# SCH_ACSI2STM-MINI_2026-07-24.net
KiCad netlist of a schematic drawn in EasyEDA
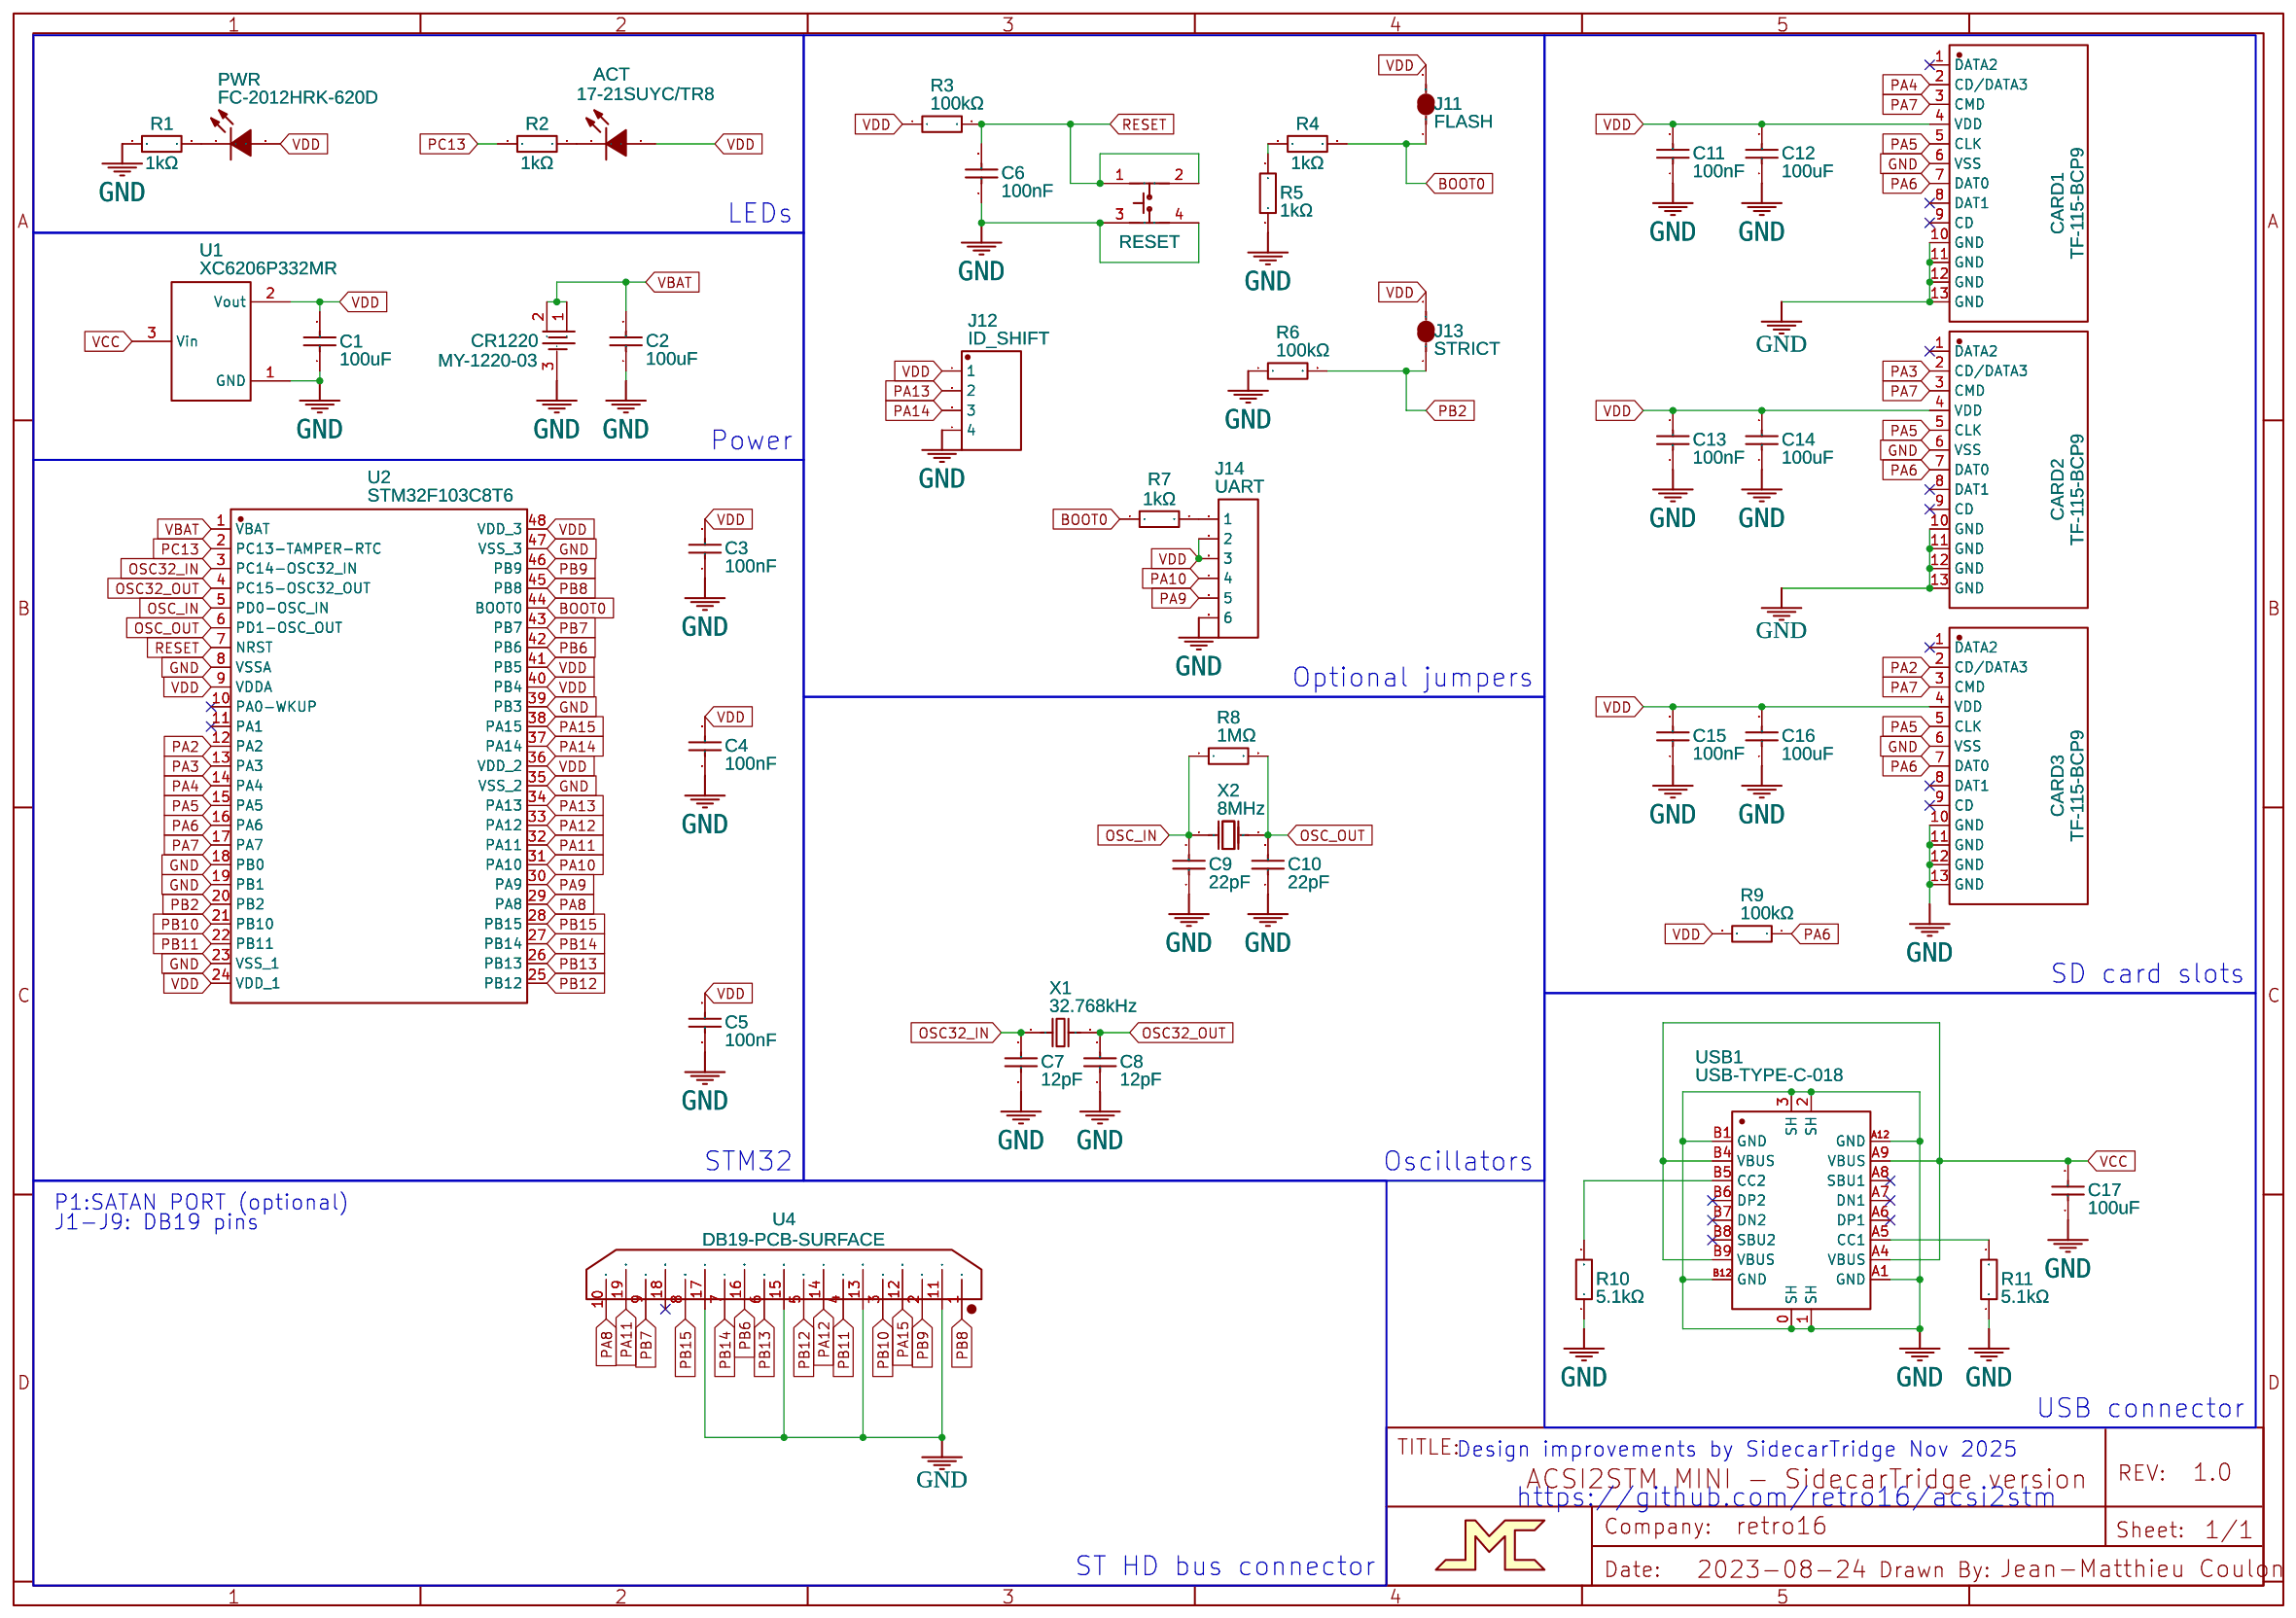
[diagram p0: schematic sheet]

(export (version "E")
  (design (tool "Eeschema 10.0.6"))
  (components
    (comp (ref "ACT")
      (value "17-21SUYC/TR8")
      (fields (field (name "Manufacturer Part") "KT-0805黄灯") (field (name "Manufacturer") "KENTO"))
      (libsource (lib "") (part "17-21SUYC/TR8"))
    )
    (comp (ref "C1")
      (value "100uF")
      (fields
        (field (name "Manufacturer Part") "CL31A107MQHNNNE")
        (field (name "Manufacturer") "SAMSUNG(三星)")
      )
      (libsource (lib "") (part "CL31A107MQHNNNE"))
    )
    (comp (ref "C2")
      (value "100uF")
      (fields
        (field (name "Manufacturer Part") "CL31A107MQHNNNE")
        (field (name "Manufacturer") "SAMSUNG(三星)")
      )
      (libsource (lib "") (part "CL31A107MQHNNNE"))
    )
    (comp (ref "C3")
      (value "100nF")
      (fields
        (field (name "Manufacturer Part") "CL05B104KO5NNNC")
        (field (name "Manufacturer") "SAMSUNG(三星)")
      )
      (libsource (lib "") (part "CL05B104KO5NNNC"))
    )
    (comp (ref "C4")
      (value "100nF")
      (fields
        (field (name "Manufacturer Part") "CL05B104KO5NNNC")
        (field (name "Manufacturer") "SAMSUNG(三星)")
      )
      (libsource (lib "") (part "CL05B104KO5NNNC"))
    )
    (comp (ref "C5")
      (value "100nF")
      (fields
        (field (name "Manufacturer Part") "CL05B104KO5NNNC")
        (field (name "Manufacturer") "SAMSUNG(三星)")
      )
      (libsource (lib "") (part "CL05B104KO5NNNC"))
    )
    (comp (ref "C6")
      (value "100nF")
      (fields
        (field (name "Manufacturer Part") "CL05B104KO5NNNC")
        (field (name "Manufacturer") "SAMSUNG(三星)")
      )
      (libsource (lib "") (part "CL05B104KO5NNNC"))
    )
    (comp (ref "C7")
      (value "12pF")
      (fields (field (name "Manufacturer Part") "0402CG120J500NT") (field (name "Manufacturer") "FH(风华)"))
      (libsource (lib "") (part "0402CG120J500NT"))
    )
    (comp (ref "C8")
      (value "12pF")
      (fields (field (name "Manufacturer Part") "0402CG120J500NT") (field (name "Manufacturer") "FH(风华)"))
      (libsource (lib "") (part "0402CG120J500NT"))
    )
    (comp (ref "C9")
      (value "22pF")
      (fields (field (name "Manufacturer Part") "0402CG220J500NT") (field (name "Manufacturer") "FH(风华)"))
      (libsource (lib "") (part "0402CG220J500NT"))
    )
    (comp (ref "C10")
      (value "22pF")
      (fields (field (name "Manufacturer Part") "0402CG220J500NT") (field (name "Manufacturer") "FH(风华)"))
      (libsource (lib "") (part "0402CG220J500NT"))
    )
    (comp (ref "C11")
      (value "100nF")
      (fields
        (field (name "Manufacturer Part") "CL05B104KO5NNNC")
        (field (name "Manufacturer") "SAMSUNG(三星)")
      )
      (libsource (lib "") (part "CL05B104KO5NNNC"))
    )
    (comp (ref "C12")
      (value "100uF")
      (fields
        (field (name "Manufacturer Part") "CL31A107MQHNNNE")
        (field (name "Manufacturer") "SAMSUNG(三星)")
      )
      (libsource (lib "") (part "CL31A107MQHNNNE"))
    )
    (comp (ref "C13")
      (value "100nF")
      (fields
        (field (name "Manufacturer Part") "CL05B104KO5NNNC")
        (field (name "Manufacturer") "SAMSUNG(三星)")
      )
      (libsource (lib "") (part "CL05B104KO5NNNC"))
    )
    (comp (ref "C14")
      (value "100uF")
      (fields
        (field (name "Manufacturer Part") "CL31A107MQHNNNE")
        (field (name "Manufacturer") "SAMSUNG(三星)")
      )
      (libsource (lib "") (part "CL31A107MQHNNNE"))
    )
    (comp (ref "C15")
      (value "100nF")
      (fields
        (field (name "Manufacturer Part") "CL31B104KBCNNNC")
        (field (name "Manufacturer") "SAMSUNG(三星)")
      )
      (libsource (lib "") (part "CL31B104KBCNNNC"))
    )
    (comp (ref "C16")
      (value "100uF")
      (fields
        (field (name "Manufacturer Part") "CL31A107MQHNNNE")
        (field (name "Manufacturer") "SAMSUNG(三星)")
      )
      (libsource (lib "") (part "CL31A107MQHNNNE"))
    )
    (comp (ref "C17")
      (value "100uF")
      (fields
        (field (name "Manufacturer Part") "CL31A107MQHNNNE")
        (field (name "Manufacturer") "SAMSUNG(三星)")
      )
      (libsource (lib "") (part "CL31A107MQHNNNE"))
    )
    (comp (ref "CARD1")
      (value "TF-115-BCP9")
      (fields (field (name "Manufacturer") "XUNPU(讯普)"))
      (libsource (lib "") (part "TF-115-BCP9"))
    )
    (comp (ref "CARD2")
      (value "TF-115-BCP9")
      (fields (field (name "Manufacturer") "XUNPU(讯普)"))
      (libsource (lib "") (part "TF-115-BCP9"))
    )
    (comp (ref "CARD3")
      (value "TF-115-BCP9")
      (fields (field (name "Manufacturer") "XUNPU(讯普)"))
      (libsource (lib "") (part "TF-115-BCP9"))
    )
    (comp (ref "CR1220")
      (value "MY-1220-03")
      (fields (field (name "Manufacturer") "MYOUNG(美阳)"))
      (libsource (lib "") (part "MY-1220-03"))
    )
    (comp (ref "J11") (value "FLASH") (libsource (lib "") (part "SOLDERJUMPERNO")))
    (comp (ref "J12") (value "ID_SHIFT") (libsource (lib "") (part "SJ-4PAD")))
    (comp (ref "J13") (value "STRICT") (libsource (lib "") (part "SOLDERJUMPERNO")))
    (comp (ref "J14") (value "UART") (libsource (lib "") (part "HDR-F-2.54_1x6")))
    (comp (ref "PWR")
      (value "FC-2012HRK-620D")
      (fields (field (name "Manufacturer Part") "NCD0805R1") (field (name "Manufacturer") "国星光电"))
      (libsource (lib "") (part "FC-2012HRK-620D"))
    )
    (comp (ref "R1")
      (value "1kΩ")
      (fields
        (field (name "Manufacturer Part") "0402WGF1001TCE")
        (field (name "Manufacturer") "UNI-ROYAL(厚声)")
      )
      (libsource (lib "") (part "0402WGF1001TCE"))
    )
    (comp (ref "R2")
      (value "1kΩ")
      (fields
        (field (name "Manufacturer Part") "0402WGF1001TCE")
        (field (name "Manufacturer") "UNI-ROYAL(厚声)")
      )
      (libsource (lib "") (part "0402WGF1001TCE"))
    )
    (comp (ref "R3")
      (value "100kΩ")
      (fields
        (field (name "Manufacturer Part") "0402WGF1003TCE")
        (field (name "Manufacturer") "UNI-ROYAL(厚声)")
      )
      (libsource (lib "") (part "0402WGF1003TCE"))
    )
    (comp (ref "R4")
      (value "1kΩ")
      (fields
        (field (name "Manufacturer Part") "0402WGF1001TCE")
        (field (name "Manufacturer") "UNI-ROYAL(厚声)")
      )
      (libsource (lib "") (part "0402WGF1001TCE"))
    )
    (comp (ref "R5")
      (value "1kΩ")
      (fields
        (field (name "Manufacturer Part") "0402WGF1001TCE")
        (field (name "Manufacturer") "UNI-ROYAL(厚声)")
      )
      (libsource (lib "") (part "0402WGF1001TCE_1"))
    )
    (comp (ref "R6")
      (value "100kΩ")
      (fields
        (field (name "Manufacturer Part") "0402WGF1003TCE")
        (field (name "Manufacturer") "UNI-ROYAL(厚声)")
      )
      (libsource (lib "") (part "0402WGF1003TCE"))
    )
    (comp (ref "R7")
      (value "1kΩ")
      (fields
        (field (name "Manufacturer Part") "0402WGF1001TCE")
        (field (name "Manufacturer") "UNI-ROYAL(厚声)")
      )
      (libsource (lib "") (part "0402WGF1001TCE"))
    )
    (comp (ref "R8")
      (value "1MΩ")
      (fields
        (field (name "Manufacturer Part") "0402WGF1004TCE")
        (field (name "Manufacturer") "UNI-ROYAL(厚声)")
      )
      (libsource (lib "") (part "0402WGF1004TCE"))
    )
    (comp (ref "R9")
      (value "100kΩ")
      (fields
        (field (name "Manufacturer Part") "0402WGF1003TCE")
        (field (name "Manufacturer") "UNI-ROYAL(厚声)")
      )
      (libsource (lib "") (part "0402WGF1003TCE_1"))
    )
    (comp (ref "R10")
      (value "5.1kΩ")
      (fields
        (field (name "Manufacturer Part") "0402WGF5101TCE")
        (field (name "Manufacturer") "UNI-ROYAL(厚声)")
      )
      (libsource (lib "") (part "0402WGF5101TCE"))
    )
    (comp (ref "R11")
      (value "5.1kΩ")
      (fields
        (field (name "Manufacturer Part") "0402WGF5101TCE")
        (field (name "Manufacturer") "UNI-ROYAL(厚声)")
      )
      (libsource (lib "") (part "0402WGF5101TCE"))
    )
    (comp (ref "RESET")
      (value "SKRPABE010")
      (fields (field (name "Manufacturer") "ALPSALPINE(阿尔卑斯阿尔派)"))
      (libsource (lib "") (part "SKRPABE010"))
    )
    (comp (ref "U1")
      (value "XC6206P332MR")
      (fields (field (name "Manufacturer") "TOREX(特瑞仕)"))
      (libsource (lib "") (part "XC6206P332MR"))
    )
    (comp (ref "U2")
      (value "STM32F103C8T6")
      (fields (field (name "Manufacturer") "ST(意法半导体)"))
      (libsource (lib "") (part "STM32F103C8T6"))
    )
    (comp (ref "U3") (value "JMC_LOGO") (libsource (lib "") (part "JMC_LOGO")))
    (comp (ref "U4") (value "DB19-PCB-SURFACE") (libsource (lib "") (part "DB19-PCB-SURFACE")))
    (comp (ref "USB1")
      (value "USB-TYPE-C-018")
      (fields (field (name "Manufacturer") "DEALON(德艺隆)"))
      (libsource (lib "") (part "USB-TYPE-C-018"))
    )
    (comp (ref "X1")
      (value "32.768kHz")
      (fields (field (name "Manufacturer Part") "Q13FC1350000400") (field (name "Manufacturer") "EPSON(爱普生)"))
      (libsource (lib "") (part "Q13FC1350000400"))
    )
    (comp (ref "X2")
      (value "8MHz")
      (fields (field (name "Manufacturer Part") "X50328MSB2GI") (field (name "Manufacturer") "YXC(扬兴晶振)"))
      (libsource (lib "") (part "X50328MSB2GI"))
    )
  )
  (nets
    (net (code "1") (name "BOOT0") (class "Default")
      (node (ref "J11") (pin "1") (pinfunction "1_1") (pintype "unspecified"))
      (node (ref "R4") (pin "2") (pinfunction "2_2") (pintype "input"))
      (node (ref "R7") (pin "1") (pinfunction "1_1") (pintype "input"))
      (node (ref "U2") (pin "44") (pinfunction "BOOT0_44") (pintype "unspecified"))
    )
    (net (code "2") (name "GND") (class "Default")
      (node (ref "C1") (pin "1") (pinfunction "1_1") (pintype "input"))
      (node (ref "C10") (pin "1") (pinfunction "1_1") (pintype "input"))
      (node (ref "C11") (pin "1") (pinfunction "1_1") (pintype "input"))
      (node (ref "C12") (pin "1") (pinfunction "1_1") (pintype "input"))
      (node (ref "C13") (pin "1") (pinfunction "1_1") (pintype "input"))
      (node (ref "C14") (pin "1") (pinfunction "1_1") (pintype "input"))
      (node (ref "C15") (pin "1") (pinfunction "1_1") (pintype "input"))
      (node (ref "C16") (pin "1") (pinfunction "1_1") (pintype "input"))
      (node (ref "C17") (pin "1") (pinfunction "1_1") (pintype "input"))
      (node (ref "C2") (pin "1") (pinfunction "1_1") (pintype "input"))
      (node (ref "C3") (pin "1") (pinfunction "1_1") (pintype "input"))
      (node (ref "C4") (pin "1") (pinfunction "1_1") (pintype "input"))
      (node (ref "C5") (pin "1") (pinfunction "1_1") (pintype "input"))
      (node (ref "C6") (pin "1") (pinfunction "1_1") (pintype "input"))
      (node (ref "C7") (pin "2") (pinfunction "2_2") (pintype "input"))
      (node (ref "C8") (pin "2") (pinfunction "2_2") (pintype "input"))
      (node (ref "C9") (pin "1") (pinfunction "1_1") (pintype "input"))
      (node (ref "CARD1") (pin "10") (pinfunction "GND_10") (pintype "unspecified"))
      (node (ref "CARD1") (pin "11") (pinfunction "GND_11") (pintype "unspecified"))
      (node (ref "CARD1") (pin "12") (pinfunction "GND_12") (pintype "unspecified"))
      (node (ref "CARD1") (pin "13") (pinfunction "GND_13") (pintype "unspecified"))
      (node (ref "CARD1") (pin "6") (pinfunction "VSS_6") (pintype "unspecified"))
      (node (ref "CARD2") (pin "10") (pinfunction "GND_10") (pintype "unspecified"))
      (node (ref "CARD2") (pin "11") (pinfunction "GND_11") (pintype "unspecified"))
      (node (ref "CARD2") (pin "12") (pinfunction "GND_12") (pintype "unspecified"))
      (node (ref "CARD2") (pin "13") (pinfunction "GND_13") (pintype "unspecified"))
      (node (ref "CARD2") (pin "6") (pinfunction "VSS_6") (pintype "unspecified"))
      (node (ref "CARD3") (pin "10") (pinfunction "GND_10") (pintype "unspecified"))
      (node (ref "CARD3") (pin "11") (pinfunction "GND_11") (pintype "unspecified"))
      (node (ref "CARD3") (pin "12") (pinfunction "GND_12") (pintype "unspecified"))
      (node (ref "CARD3") (pin "13") (pinfunction "GND_13") (pintype "unspecified"))
      (node (ref "CARD3") (pin "6") (pinfunction "VSS_6") (pintype "unspecified"))
      (node (ref "CR1220") (pin "3") (pinfunction "-_3") (pintype "input"))
      (node (ref "J12") (pin "4") (pinfunction "4_4") (pintype "unspecified"))
      (node (ref "J14") (pin "6") (pinfunction "6_6") (pintype "input"))
      (node (ref "R1") (pin "1") (pinfunction "1_1") (pintype "input"))
      (node (ref "R10") (pin "1") (pinfunction "1_1") (pintype "input"))
      (node (ref "R11") (pin "1") (pinfunction "1_1") (pintype "input"))
      (node (ref "R5") (pin "1") (pinfunction "1_1") (pintype "input"))
      (node (ref "R6") (pin "1") (pinfunction "1_1") (pintype "input"))
      (node (ref "RESET") (pin "3") (pinfunction "3_3") (pintype "unspecified"))
      (node (ref "RESET") (pin "4") (pinfunction "4_4") (pintype "unspecified"))
      (node (ref "U1") (pin "1") (pinfunction "GND_1") (pintype "unspecified"))
      (node (ref "U2") (pin "18") (pinfunction "PB0_18") (pintype "unspecified"))
      (node (ref "U2") (pin "19") (pinfunction "PB1_19") (pintype "unspecified"))
      (node (ref "U2") (pin "23") (pinfunction "VSS_1_23") (pintype "unspecified"))
      (node (ref "U2") (pin "35") (pinfunction "VSS_2_35") (pintype "unspecified"))
      (node (ref "U2") (pin "39") (pinfunction "PB3_39") (pintype "unspecified"))
      (node (ref "U2") (pin "47") (pinfunction "VSS_3_47") (pintype "unspecified"))
      (node (ref "U2") (pin "8") (pinfunction "VSSA_8") (pintype "unspecified"))
      (node (ref "U4") (pin "11") (pinfunction "11_11") (pintype "unspecified"))
      (node (ref "U4") (pin "13") (pinfunction "13_13") (pintype "unspecified"))
      (node (ref "U4") (pin "15") (pinfunction "15_15") (pintype "unspecified"))
      (node (ref "U4") (pin "17") (pinfunction "17_17") (pintype "unspecified"))
      (node (ref "USB1") (pin "0") (pinfunction "SH_0") (pintype "unspecified"))
      (node (ref "USB1") (pin "1") (pinfunction "SH_1") (pintype "unspecified"))
      (node (ref "USB1") (pin "2") (pinfunction "SH_2") (pintype "unspecified"))
      (node (ref "USB1") (pin "3") (pinfunction "SH_3") (pintype "unspecified"))
      (node (ref "USB1") (pin "A1") (pinfunction "GND_A1") (pintype "unspecified"))
      (node (ref "USB1") (pin "A12") (pinfunction "GND_A12") (pintype "unspecified"))
      (node (ref "USB1") (pin "B1") (pinfunction "GND_B1") (pintype "unspecified"))
      (node (ref "USB1") (pin "B12") (pinfunction "GND_B12") (pintype "unspecified"))
    )
    (net (code "3") (name "Net-(ACT--)") (class "Default")
      (node (ref "ACT") (pin "2") (pinfunction "-_2") (pintype "unspecified"))
      (node (ref "R2") (pin "2") (pinfunction "2_2") (pintype "input"))
    )
    (net (code "4") (name "Net-(J14-Pad1)") (class "Default")
      (node (ref "J14") (pin "1") (pinfunction "1_1") (pintype "input"))
      (node (ref "R7") (pin "2") (pinfunction "2_2") (pintype "input"))
    )
    (net (code "5") (name "Net-(PWR--)") (class "Default")
      (node (ref "PWR") (pin "1") (pinfunction "-_1") (pintype "unspecified"))
      (node (ref "R1") (pin "2") (pinfunction "2_2") (pintype "input"))
    )
    (net (code "6") (name "Net-(R4-Pad1)") (class "Default")
      (node (ref "R4") (pin "1") (pinfunction "1_1") (pintype "input"))
      (node (ref "R5") (pin "2") (pinfunction "2_2") (pintype "input"))
    )
    (net (code "7") (name "Net-(USB1-CC1)") (class "Default")
      (node (ref "R11") (pin "2") (pinfunction "2_2") (pintype "input"))
      (node (ref "USB1") (pin "A5") (pinfunction "CC1_A5") (pintype "unspecified"))
    )
    (net (code "8") (name "Net-(USB1-CC2)") (class "Default")
      (node (ref "R10") (pin "2") (pinfunction "2_2") (pintype "input"))
      (node (ref "USB1") (pin "B5") (pinfunction "CC2_B5") (pintype "unspecified"))
    )
    (net (code "9") (name "OSC32_IN") (class "Default")
      (node (ref "C7") (pin "1") (pinfunction "1_1") (pintype "input"))
      (node (ref "U2") (pin "3") (pinfunction "PC14-OSC32_IN_3") (pintype "unspecified"))
      (node (ref "X1") (pin "1") (pinfunction "1_1") (pintype "unspecified"))
    )
    (net (code "10") (name "OSC32_OUT") (class "Default")
      (node (ref "C8") (pin "1") (pinfunction "1_1") (pintype "input"))
      (node (ref "U2") (pin "4") (pinfunction "PC15-OSC32_OUT_4") (pintype "unspecified"))
      (node (ref "X1") (pin "2") (pinfunction "2_2") (pintype "unspecified"))
    )
    (net (code "11") (name "OSC_IN") (class "Default")
      (node (ref "C9") (pin "2") (pinfunction "2_2") (pintype "input"))
      (node (ref "R8") (pin "1") (pinfunction "1_1") (pintype "input"))
      (node (ref "U2") (pin "5") (pinfunction "PD0-OSC_IN_5") (pintype "unspecified"))
      (node (ref "X2") (pin "1") (pinfunction "OSC1_1") (pintype "input"))
    )
    (net (code "12") (name "OSC_OUT") (class "Default")
      (node (ref "C10") (pin "2") (pinfunction "2_2") (pintype "input"))
      (node (ref "R8") (pin "2") (pinfunction "2_2") (pintype "input"))
      (node (ref "U2") (pin "6") (pinfunction "PD1-OSC_OUT_6") (pintype "unspecified"))
      (node (ref "X2") (pin "2") (pinfunction "OSC2_2") (pintype "input"))
    )
    (net (code "13") (name "PA2") (class "Default")
      (node (ref "CARD3") (pin "2") (pinfunction "CD/DATA3_2") (pintype "unspecified"))
      (node (ref "U2") (pin "12") (pinfunction "PA2_12") (pintype "unspecified"))
    )
    (net (code "14") (name "PA3") (class "Default")
      (node (ref "CARD2") (pin "2") (pinfunction "CD/DATA3_2") (pintype "unspecified"))
      (node (ref "U2") (pin "13") (pinfunction "PA3_13") (pintype "unspecified"))
    )
    (net (code "15") (name "PA4") (class "Default")
      (node (ref "CARD1") (pin "2") (pinfunction "CD/DATA3_2") (pintype "unspecified"))
      (node (ref "U2") (pin "14") (pinfunction "PA4_14") (pintype "unspecified"))
    )
    (net (code "16") (name "PA5") (class "Default")
      (node (ref "CARD1") (pin "5") (pinfunction "CLK_5") (pintype "unspecified"))
      (node (ref "CARD2") (pin "5") (pinfunction "CLK_5") (pintype "unspecified"))
      (node (ref "CARD3") (pin "5") (pinfunction "CLK_5") (pintype "unspecified"))
      (node (ref "U2") (pin "15") (pinfunction "PA5_15") (pintype "unspecified"))
    )
    (net (code "17") (name "PA6") (class "Default")
      (node (ref "CARD1") (pin "7") (pinfunction "DAT0_7") (pintype "unspecified"))
      (node (ref "CARD2") (pin "7") (pinfunction "DAT0_7") (pintype "unspecified"))
      (node (ref "CARD3") (pin "7") (pinfunction "DAT0_7") (pintype "unspecified"))
      (node (ref "R9") (pin "1") (pinfunction "1_1") (pintype "input"))
      (node (ref "U2") (pin "16") (pinfunction "PA6_16") (pintype "unspecified"))
    )
    (net (code "18") (name "PA7") (class "Default")
      (node (ref "CARD1") (pin "3") (pinfunction "CMD_3") (pintype "unspecified"))
      (node (ref "CARD2") (pin "3") (pinfunction "CMD_3") (pintype "unspecified"))
      (node (ref "CARD3") (pin "3") (pinfunction "CMD_3") (pintype "unspecified"))
      (node (ref "U2") (pin "17") (pinfunction "PA7_17") (pintype "unspecified"))
    )
    (net (code "19") (name "PA8") (class "Default")
      (node (ref "U2") (pin "29") (pinfunction "PA8_29") (pintype "unspecified"))
      (node (ref "U4") (pin "10") (pinfunction "10_10") (pintype "unspecified"))
    )
    (net (code "20") (name "PA9") (class "Default")
      (node (ref "J14") (pin "5") (pinfunction "5_5") (pintype "input"))
      (node (ref "U2") (pin "30") (pinfunction "PA9_30") (pintype "unspecified"))
    )
    (net (code "21") (name "PA10") (class "Default")
      (node (ref "J14") (pin "4") (pinfunction "4_4") (pintype "input"))
      (node (ref "U2") (pin "31") (pinfunction "PA10_31") (pintype "unspecified"))
    )
    (net (code "22") (name "PA11") (class "Default")
      (node (ref "U2") (pin "32") (pinfunction "PA11_32") (pintype "unspecified"))
      (node (ref "U4") (pin "19") (pinfunction "19_19") (pintype "unspecified"))
    )
    (net (code "23") (name "PA12") (class "Default")
      (node (ref "U2") (pin "33") (pinfunction "PA12_33") (pintype "unspecified"))
      (node (ref "U4") (pin "14") (pinfunction "14_14") (pintype "unspecified"))
    )
    (net (code "24") (name "PA13") (class "Default")
      (node (ref "J12") (pin "2") (pinfunction "2_2") (pintype "unspecified"))
      (node (ref "U2") (pin "34") (pinfunction "PA13_34") (pintype "unspecified"))
    )
    (net (code "25") (name "PA14") (class "Default")
      (node (ref "J12") (pin "3") (pinfunction "3_3") (pintype "unspecified"))
      (node (ref "U2") (pin "37") (pinfunction "PA14_37") (pintype "unspecified"))
    )
    (net (code "26") (name "PA15") (class "Default")
      (node (ref "U2") (pin "38") (pinfunction "PA15_38") (pintype "unspecified"))
      (node (ref "U4") (pin "12") (pinfunction "12_12") (pintype "unspecified"))
    )
    (net (code "27") (name "PB2") (class "Default")
      (node (ref "J13") (pin "1") (pinfunction "1_1") (pintype "unspecified"))
      (node (ref "R6") (pin "2") (pinfunction "2_2") (pintype "input"))
      (node (ref "U2") (pin "20") (pinfunction "PB2_20") (pintype "unspecified"))
    )
    (net (code "28") (name "PB6") (class "Default")
      (node (ref "U2") (pin "42") (pinfunction "PB6_42") (pintype "unspecified"))
      (node (ref "U4") (pin "16") (pinfunction "16_16") (pintype "unspecified"))
    )
    (net (code "29") (name "PB7") (class "Default")
      (node (ref "U2") (pin "43") (pinfunction "PB7_43") (pintype "unspecified"))
      (node (ref "U4") (pin "9") (pinfunction "9_9") (pintype "unspecified"))
    )
    (net (code "30") (name "PB8") (class "Default")
      (node (ref "U2") (pin "45") (pinfunction "PB8_45") (pintype "unspecified"))
      (node (ref "U4") (pin "1") (pinfunction "1_1") (pintype "unspecified"))
    )
    (net (code "31") (name "PB9") (class "Default")
      (node (ref "U2") (pin "46") (pinfunction "PB9_46") (pintype "unspecified"))
      (node (ref "U4") (pin "2") (pinfunction "2_2") (pintype "unspecified"))
    )
    (net (code "32") (name "PB10") (class "Default")
      (node (ref "U2") (pin "21") (pinfunction "PB10_21") (pintype "unspecified"))
      (node (ref "U4") (pin "3") (pinfunction "3_3") (pintype "unspecified"))
    )
    (net (code "33") (name "PB11") (class "Default")
      (node (ref "U2") (pin "22") (pinfunction "PB11_22") (pintype "unspecified"))
      (node (ref "U4") (pin "4") (pinfunction "4_4") (pintype "unspecified"))
    )
    (net (code "34") (name "PB12") (class "Default")
      (node (ref "U2") (pin "25") (pinfunction "PB12_25") (pintype "unspecified"))
      (node (ref "U4") (pin "5") (pinfunction "5_5") (pintype "unspecified"))
    )
    (net (code "35") (name "PB13") (class "Default")
      (node (ref "U2") (pin "26") (pinfunction "PB13_26") (pintype "unspecified"))
      (node (ref "U4") (pin "6") (pinfunction "6_6") (pintype "unspecified"))
    )
    (net (code "36") (name "PB14") (class "Default")
      (node (ref "U2") (pin "27") (pinfunction "PB14_27") (pintype "unspecified"))
      (node (ref "U4") (pin "7") (pinfunction "7_7") (pintype "unspecified"))
    )
    (net (code "37") (name "PB15") (class "Default")
      (node (ref "U2") (pin "28") (pinfunction "PB15_28") (pintype "unspecified"))
      (node (ref "U4") (pin "8") (pinfunction "8_8") (pintype "unspecified"))
    )
    (net (code "38") (name "PC13") (class "Default")
      (node (ref "R2") (pin "1") (pinfunction "1_1") (pintype "input"))
      (node (ref "U2") (pin "2") (pinfunction "PC13-TAMPER-RTC_2") (pintype "unspecified"))
    )
    (net (code "39") (name "RESET") (class "Default")
      (node (ref "C6") (pin "2") (pinfunction "2_2") (pintype "input"))
      (node (ref "R3") (pin "2") (pinfunction "2_2") (pintype "input"))
      (node (ref "RESET") (pin "1") (pinfunction "1_1") (pintype "unspecified"))
      (node (ref "RESET") (pin "2") (pinfunction "2_2") (pintype "unspecified"))
      (node (ref "U2") (pin "7") (pinfunction "NRST_7") (pintype "unspecified"))
    )
    (net (code "40") (name "VBAT") (class "Default")
      (node (ref "C2") (pin "2") (pinfunction "2_2") (pintype "input"))
      (node (ref "CR1220") (pin "1") (pinfunction "+_1") (pintype "input"))
      (node (ref "CR1220") (pin "2") (pinfunction "+_2") (pintype "input"))
      (node (ref "U2") (pin "1") (pinfunction "VBAT_1") (pintype "unspecified"))
    )
    (net (code "41") (name "VCC") (class "Default")
      (node (ref "C17") (pin "2") (pinfunction "2_2") (pintype "input"))
      (node (ref "U1") (pin "3") (pinfunction "Vin_3") (pintype "unspecified"))
      (node (ref "USB1") (pin "A4") (pinfunction "VBUS_A4") (pintype "unspecified"))
      (node (ref "USB1") (pin "A9") (pinfunction "VBUS_A9") (pintype "unspecified"))
      (node (ref "USB1") (pin "B4") (pinfunction "VBUS_B4") (pintype "unspecified"))
      (node (ref "USB1") (pin "B9") (pinfunction "VBUS_B9") (pintype "unspecified"))
    )
    (net (code "42") (name "VDD") (class "Default")
      (node (ref "ACT") (pin "1") (pinfunction "+_1") (pintype "unspecified"))
      (node (ref "C1") (pin "2") (pinfunction "2_2") (pintype "input"))
      (node (ref "C11") (pin "2") (pinfunction "2_2") (pintype "input"))
      (node (ref "C12") (pin "2") (pinfunction "2_2") (pintype "input"))
      (node (ref "C13") (pin "2") (pinfunction "2_2") (pintype "input"))
      (node (ref "C14") (pin "2") (pinfunction "2_2") (pintype "input"))
      (node (ref "C15") (pin "2") (pinfunction "2_2") (pintype "input"))
      (node (ref "C16") (pin "2") (pinfunction "2_2") (pintype "input"))
      (node (ref "C3") (pin "2") (pinfunction "2_2") (pintype "input"))
      (node (ref "C4") (pin "2") (pinfunction "2_2") (pintype "input"))
      (node (ref "C5") (pin "2") (pinfunction "2_2") (pintype "input"))
      (node (ref "CARD1") (pin "4") (pinfunction "VDD_4") (pintype "unspecified"))
      (node (ref "CARD2") (pin "4") (pinfunction "VDD_4") (pintype "unspecified"))
      (node (ref "CARD3") (pin "4") (pinfunction "VDD_4") (pintype "unspecified"))
      (node (ref "J11") (pin "2") (pinfunction "2_2") (pintype "unspecified"))
      (node (ref "J12") (pin "1") (pinfunction "1_1") (pintype "unspecified"))
      (node (ref "J13") (pin "2") (pinfunction "2_2") (pintype "unspecified"))
      (node (ref "J14") (pin "2") (pinfunction "2_2") (pintype "input"))
      (node (ref "J14") (pin "3") (pinfunction "3_3") (pintype "input"))
      (node (ref "PWR") (pin "2") (pinfunction "+_2") (pintype "unspecified"))
      (node (ref "R3") (pin "1") (pinfunction "1_1") (pintype "input"))
      (node (ref "R9") (pin "2") (pinfunction "2_2") (pintype "input"))
      (node (ref "U1") (pin "2") (pinfunction "Vout_2") (pintype "unspecified"))
      (node (ref "U2") (pin "24") (pinfunction "VDD_1_24") (pintype "unspecified"))
      (node (ref "U2") (pin "36") (pinfunction "VDD_2_36") (pintype "unspecified"))
      (node (ref "U2") (pin "40") (pinfunction "PB4_40") (pintype "unspecified"))
      (node (ref "U2") (pin "41") (pinfunction "PB5_41") (pintype "unspecified"))
      (node (ref "U2") (pin "48") (pinfunction "VDD_3_48") (pintype "unspecified"))
      (node (ref "U2") (pin "9") (pinfunction "VDDA_9") (pintype "unspecified"))
    )
    (net (code "43") (name "unconnected-(CARD1-CD-Pad9)") (class "Default")
      (node (ref "CARD1") (pin "9") (pinfunction "CD_9") (pintype "unspecified+no_connect"))
    )
    (net (code "44") (name "unconnected-(CARD1-DAT1-Pad8)") (class "Default")
      (node (ref "CARD1") (pin "8") (pinfunction "DAT1_8") (pintype "unspecified+no_connect"))
    )
    (net (code "45") (name "unconnected-(CARD1-DATA2-Pad1)") (class "Default")
      (node (ref "CARD1") (pin "1") (pinfunction "DATA2_1") (pintype "unspecified+no_connect"))
    )
    (net (code "46") (name "unconnected-(CARD2-CD-Pad9)") (class "Default")
      (node (ref "CARD2") (pin "9") (pinfunction "CD_9") (pintype "unspecified+no_connect"))
    )
    (net (code "47") (name "unconnected-(CARD2-DAT1-Pad8)") (class "Default")
      (node (ref "CARD2") (pin "8") (pinfunction "DAT1_8") (pintype "unspecified+no_connect"))
    )
    (net (code "48") (name "unconnected-(CARD2-DATA2-Pad1)") (class "Default")
      (node (ref "CARD2") (pin "1") (pinfunction "DATA2_1") (pintype "unspecified+no_connect"))
    )
    (net (code "49") (name "unconnected-(CARD3-CD-Pad9)") (class "Default")
      (node (ref "CARD3") (pin "9") (pinfunction "CD_9") (pintype "unspecified+no_connect"))
    )
    (net (code "50") (name "unconnected-(CARD3-DAT1-Pad8)") (class "Default")
      (node (ref "CARD3") (pin "8") (pinfunction "DAT1_8") (pintype "unspecified+no_connect"))
    )
    (net (code "51") (name "unconnected-(CARD3-DATA2-Pad1)") (class "Default")
      (node (ref "CARD3") (pin "1") (pinfunction "DATA2_1") (pintype "unspecified+no_connect"))
    )
    (net (code "52") (name "unconnected-(U2-PA0-WKUP-Pad10)") (class "Default")
      (node (ref "U2") (pin "10") (pinfunction "PA0-WKUP_10") (pintype "unspecified+no_connect"))
    )
    (net (code "53") (name "unconnected-(U2-PA1-Pad11)") (class "Default")
      (node (ref "U2") (pin "11") (pinfunction "PA1_11") (pintype "unspecified+no_connect"))
    )
    (net (code "54") (name "unconnected-(U4-Pad18)") (class "Default")
      (node (ref "U4") (pin "18") (pinfunction "18_18") (pintype "unspecified+no_connect"))
    )
    (net (code "55") (name "unconnected-(USB1-DN1-PadA7)") (class "Default")
      (node (ref "USB1") (pin "A7") (pinfunction "DN1_A7") (pintype "unspecified+no_connect"))
    )
    (net (code "56") (name "unconnected-(USB1-DN2-PadB7)") (class "Default")
      (node (ref "USB1") (pin "B7") (pinfunction "DN2_B7") (pintype "unspecified+no_connect"))
    )
    (net (code "57") (name "unconnected-(USB1-DP1-PadA6)") (class "Default")
      (node (ref "USB1") (pin "A6") (pinfunction "DP1_A6") (pintype "unspecified+no_connect"))
    )
    (net (code "58") (name "unconnected-(USB1-DP2-PadB6)") (class "Default")
      (node (ref "USB1") (pin "B6") (pinfunction "DP2_B6") (pintype "unspecified+no_connect"))
    )
    (net (code "59") (name "unconnected-(USB1-SBU1-PadA8)") (class "Default")
      (node (ref "USB1") (pin "A8") (pinfunction "SBU1_A8") (pintype "unspecified+no_connect"))
    )
    (net (code "60") (name "unconnected-(USB1-SBU2-PadB8)") (class "Default")
      (node (ref "USB1") (pin "B8") (pinfunction "SBU2_B8") (pintype "unspecified+no_connect"))
    )
  )
)
